# SBH_Charger_rp2040.net
KiCad netlist of a schematic drawn in Altium Designer
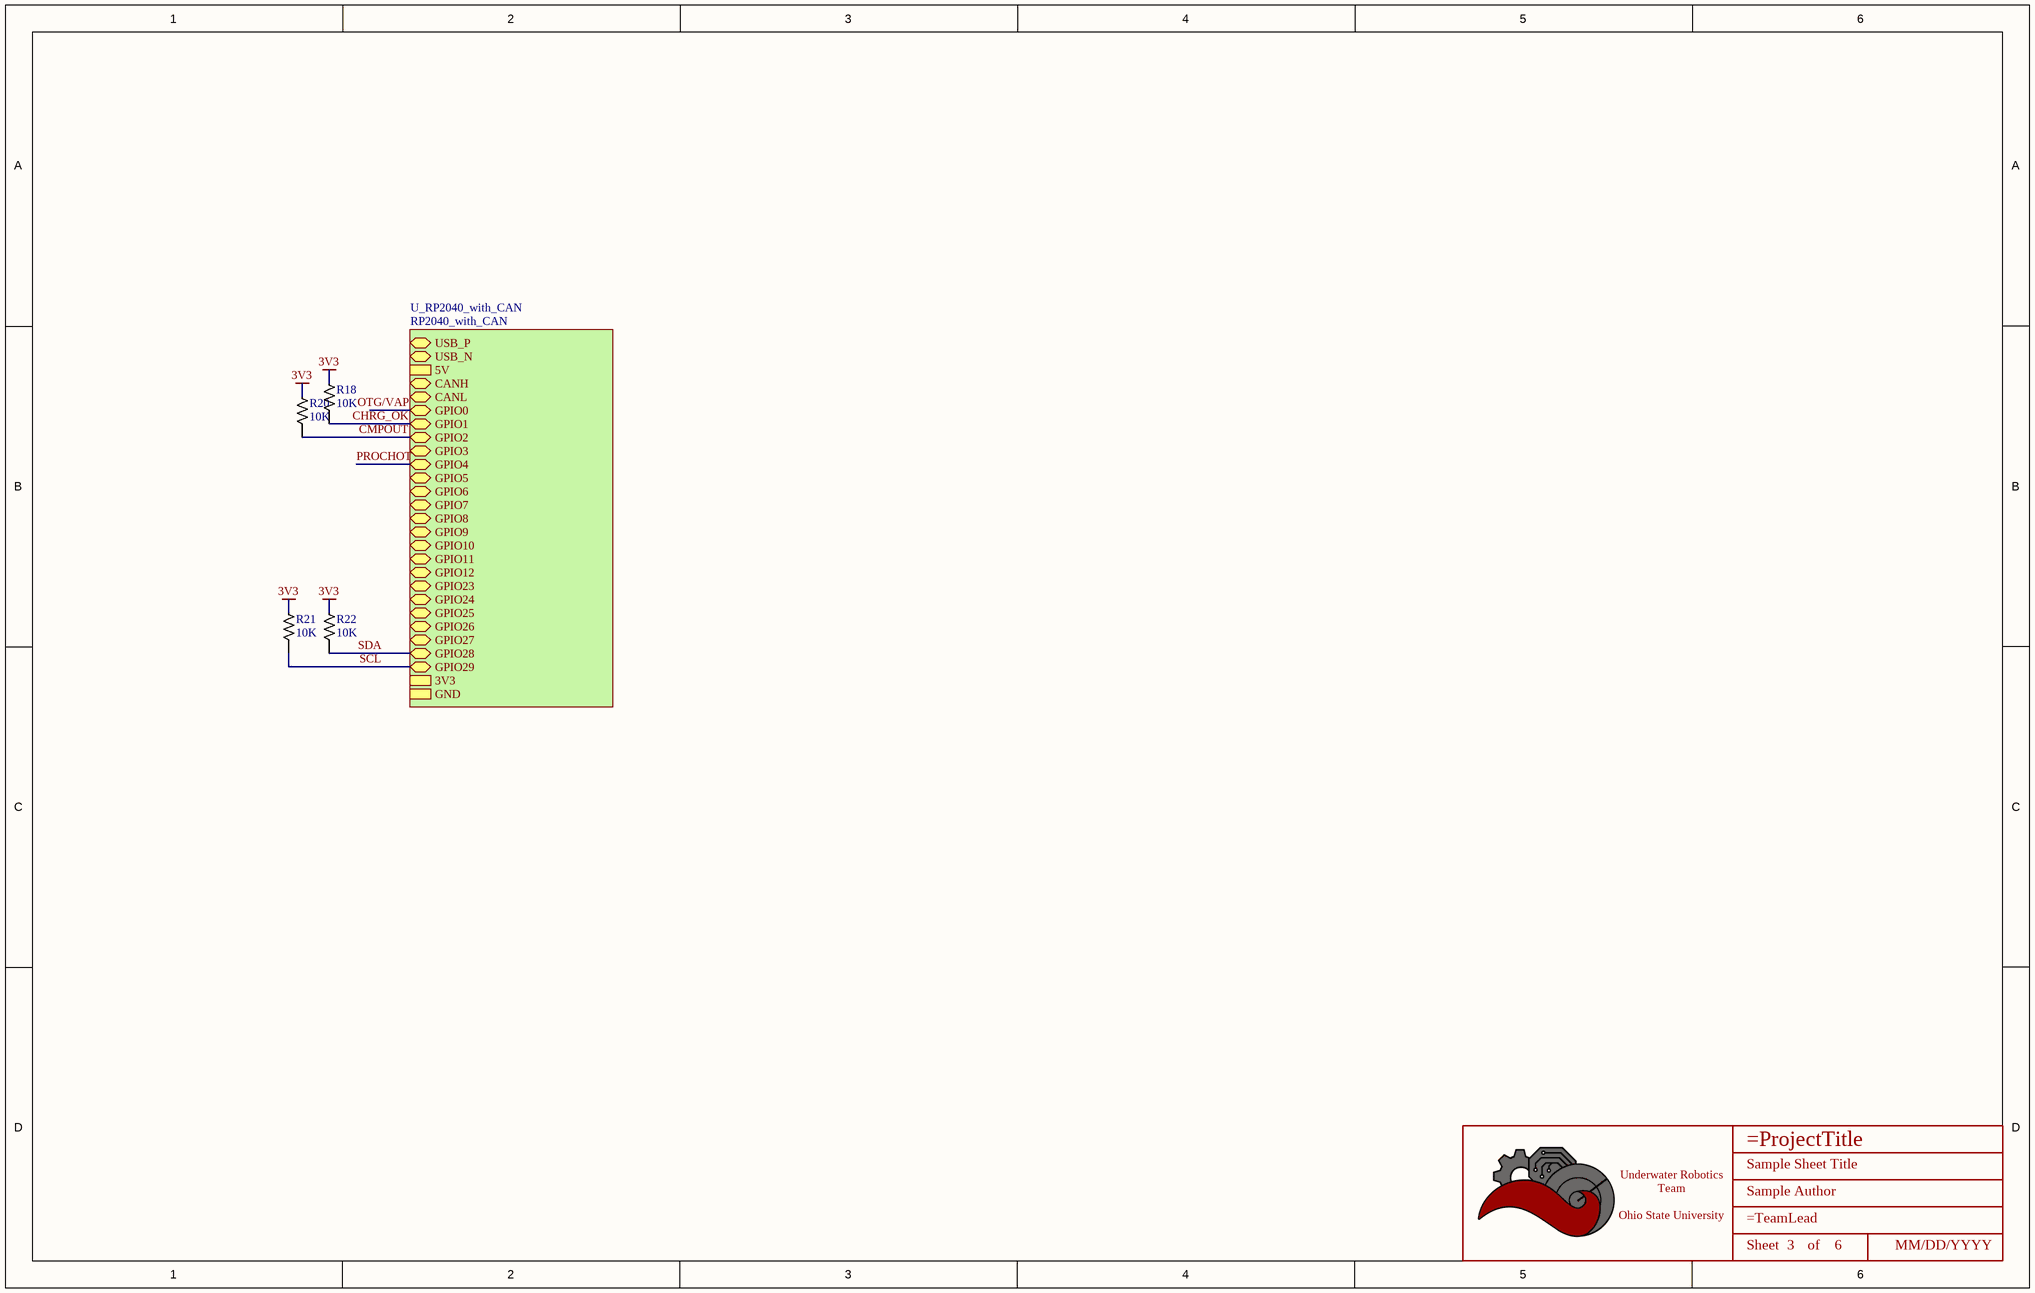
[diagram p0: SBH_Charger_rp2040.SchDoc]

(export (version "E")
  (design (tool "Eeschema 10.0.6"))
  (components
    (comp (ref "*")
      (value "Title_Block")
      (footprint "LOGO")
      (description "UWRT Schematic Title Block Template\r\n\r\nCreated June 2021, Dylan Trainor")
      (libsource (lib "UWRT") (part "Title_Block"))
    )
    (comp (ref "R18")
      (value "10k Ohm 5% 1/10W")
      (footprint "RESISTOR_0603")
      (description "RES 10k OHM 5% 1/10W 0603")
      (fields
        (field (name "TOLERANCE") "+/- 5%")
        (field (name "VALUE  (OHMS)") "10K")
        (field (name "MADE BY") "Robert Pafford")
      )
      (libsource (lib "Resistors") (part "RESISTOR_10K_0603"))
    )
    (comp (ref "R20")
      (value "10k Ohm 5% 1/10W")
      (footprint "RESISTOR_0603")
      (description "RES 10k OHM 5% 1/10W 0603")
      (fields
        (field (name "TOLERANCE") "+/- 5%")
        (field (name "VALUE  (OHMS)") "10K")
        (field (name "MADE BY") "Robert Pafford")
      )
      (libsource (lib "Resistors") (part "RESISTOR_10K_0603"))
    )
    (comp (ref "R21")
      (value "10k Ohm 5% 1/10W")
      (footprint "RESISTOR_0603")
      (description "RES 10k OHM 5% 1/10W 0603")
      (fields
        (field (name "TOLERANCE") "+/- 5%")
        (field (name "VALUE  (OHMS)") "10K")
        (field (name "MADE BY") "Robert Pafford")
      )
      (libsource (lib "Resistors") (part "RESISTOR_10K_0603"))
    )
    (comp (ref "R22")
      (value "10k Ohm 5% 1/10W")
      (footprint "RESISTOR_0603")
      (description "RES 10k OHM 5% 1/10W 0603")
      (fields
        (field (name "TOLERANCE") "+/- 5%")
        (field (name "VALUE  (OHMS)") "10K")
        (field (name "MADE BY") "Robert Pafford")
      )
      (libsource (lib "Resistors") (part "RESISTOR_10K_0603"))
    )
  )
  (nets
    (net (code "5") (name "/CHRG_OK") (class "Default")
      (node (ref "R18") (pin "2") (pinfunction "2_2") (pintype "passive"))
    )
    (net (code "6") (name "/CMPOUT") (class "Default")
      (node (ref "R20") (pin "2") (pinfunction "2_2") (pintype "passive"))
    )
    (net (code "24") (name "/SCL") (class "Default")
      (node (ref "R21") (pin "2") (pinfunction "2_2") (pintype "passive"))
    )
    (net (code "25") (name "/SDA") (class "Default")
      (node (ref "R22") (pin "2") (pinfunction "2_2") (pintype "passive"))
    )
    (net (code "28") (name "3V3") (class "Default")
      (node (ref "R18") (pin "1") (pinfunction "1_1") (pintype "passive"))
      (node (ref "R20") (pin "1") (pinfunction "1_1") (pintype "passive"))
      (node (ref "R21") (pin "1") (pinfunction "1_1") (pintype "passive"))
      (node (ref "R22") (pin "1") (pinfunction "1_1") (pintype "passive"))
    )
  )
)
